# reset_final_rev01.net
KiCad netlist of a schematic drawn in EAGLE
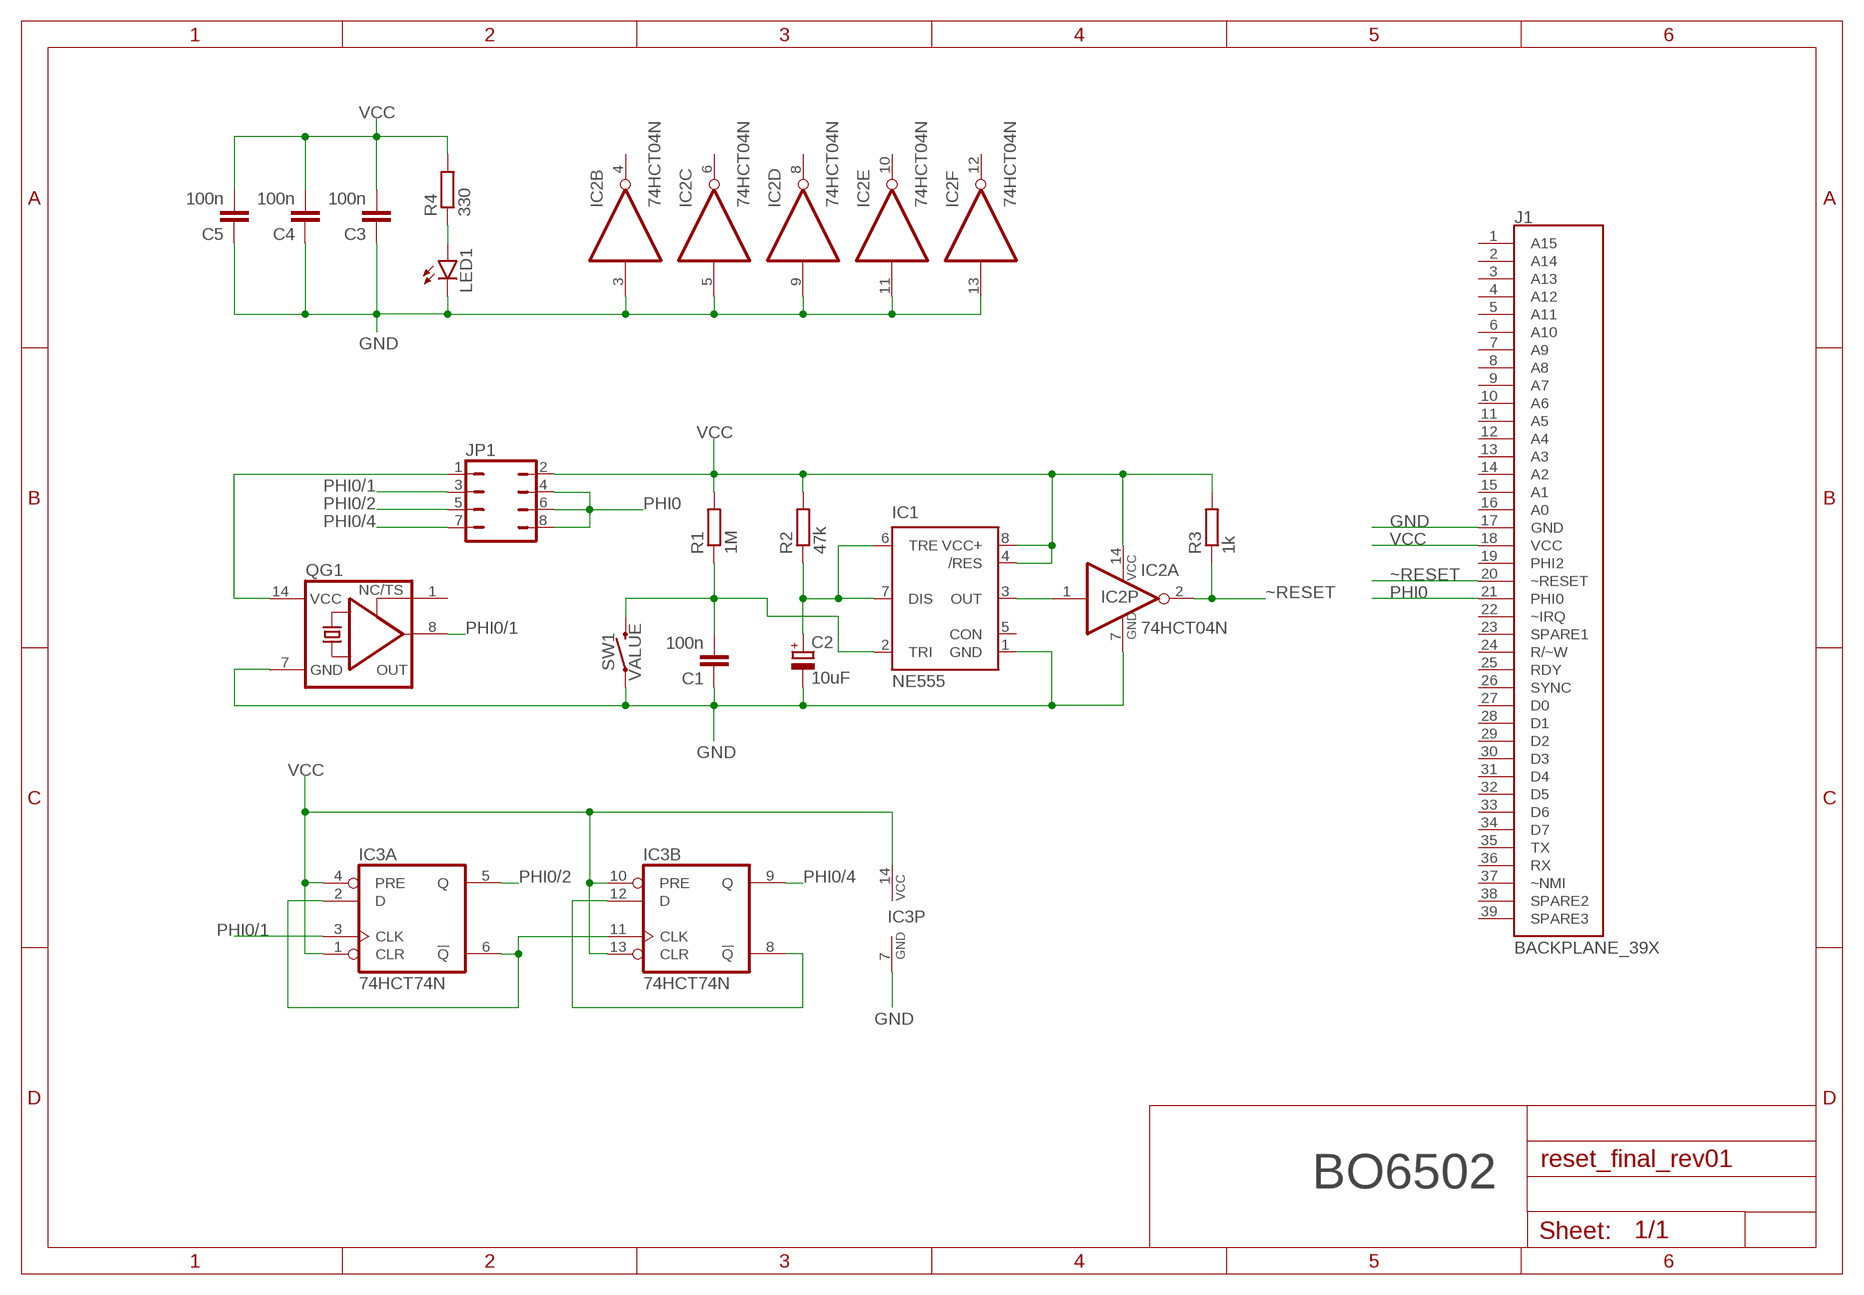
[diagram p0: schematic, sheet 1]

(export (version "E")
  (design (tool "Eeschema 10.0.6"))
  (components
    (comp (ref "C1")
      (value "100n")
      (footprint "eagle-import:C025-025X050")
      (libsource (lib "eagle-import") (part "C-EU025-025X050"))
    )
    (comp (ref "C2")
      (value "10uF")
      (footprint "eagle-import:B45181A")
      (libsource (lib "eagle-import") (part "CPOL-EUB45181A"))
    )
    (comp (ref "C3")
      (value "100n")
      (footprint "eagle-import:C025-025X050")
      (libsource (lib "eagle-import") (part "C-EU025-025X050"))
    )
    (comp (ref "C4")
      (value "100n")
      (footprint "eagle-import:C025-025X050")
      (libsource (lib "eagle-import") (part "C-EU025-025X050"))
    )
    (comp (ref "C5")
      (value "100n")
      (footprint "eagle-import:C025-025X050")
      (libsource (lib "eagle-import") (part "C-EU025-025X050"))
    )
    (comp (ref "IC1")
      (value "NE555")
      (footprint "eagle-import:DIL-08")
      (fields (field (name "MF") "Arrow Electronics") (field (name "MPN") "NE555N"))
      (libsource (lib "eagle-import") (part "NE555"))
    )
    (comp (ref "IC2")
      (value "74HCT04N")
      (footprint "eagle-import:DIL14")
      (libsource (lib "eagle-import") (part "7404NHCT"))
    )
    (comp (ref "IC3")
      (value "74HCT74N")
      (footprint "eagle-import:DIL14")
      (libsource (lib "eagle-import") (part "7474NHCT"))
    )
    (comp (ref "J1")
      (value "BACKPLANE_39X")
      (footprint "eagle-import:BP_39X")
      (fields
        (field (name "PIN_1") "A15")
        (field (name "PIN_2") "A14")
        (field (name "PIN_3") "A13")
        (field (name "PIN_4") "A12")
        (field (name "PIN_5") "A11")
        (field (name "PIN_6") "A10")
        (field (name "PIN_7") "A9")
        (field (name "PIN_8") "A8")
        (field (name "PIN_9") "A7")
      )
      (libsource (lib "eagle-import") (part "BACKPLANE_39X"))
    )
    (comp (ref "JP1")
      (value "JP4Q")
      (footprint "eagle-import:JP4Q")
      (libsource (lib "eagle-import") (part "JP4Q"))
    )
    (comp (ref "LED1")
      (value "LED5MM")
      (footprint "eagle-import:LED5MM")
      (libsource (lib "eagle-import") (part "LED5MM"))
    )
    (comp (ref "QG1")
      (value "XO-14")
      (footprint "eagle-import:DIL14S")
      (libsource (lib "eagle-import") (part "XO-14"))
    )
    (comp (ref "R1")
      (value "1M")
      (footprint "eagle-import:0207_10")
      (libsource (lib "eagle-import") (part "R-EU_0207/10"))
    )
    (comp (ref "R2")
      (value "47k")
      (footprint "eagle-import:0207_10")
      (libsource (lib "eagle-import") (part "R-EU_0207/10"))
    )
    (comp (ref "R3")
      (value "1k")
      (footprint "eagle-import:0207_10")
      (libsource (lib "eagle-import") (part "R-EU_0207/10"))
    )
    (comp (ref "R4")
      (value "330")
      (footprint "eagle-import:0207_10")
      (libsource (lib "eagle-import") (part "R-EU_0207/10"))
    )
    (comp (ref "SW1")
      (value "MOMENTARY-SWITCH-SPST-PTH-6.0MM-KIT")
      (footprint "eagle-import:TACTILE_SWITCH_PTH_6.0MM_KIT")
      (libsource (lib "eagle-import") (part "MOMENTARY-SWITCH-SPST-PTH-6.0MM-KIT"))
    )
  )
  (nets
    (net (code "1") (name "/GND") (class "Default")
      (node (ref "C1") (pin "1") (pinfunction "1_1") (pintype "passive"))
      (node (ref "C2") (pin "-") (pinfunction "-_-") (pintype "passive"))
      (node (ref "C3") (pin "1") (pinfunction "1_1") (pintype "passive"))
      (node (ref "C4") (pin "1") (pinfunction "1_1") (pintype "passive"))
      (node (ref "C5") (pin "1") (pinfunction "1_1") (pintype "passive"))
      (node (ref "IC1") (pin "1") (pinfunction "GND_1") (pintype "power_in"))
      (node (ref "IC2") (pin "11") (pinfunction "I_11") (pintype "input"))
      (node (ref "IC2") (pin "13") (pinfunction "I_13") (pintype "input"))
      (node (ref "IC2") (pin "3") (pinfunction "I_3") (pintype "input"))
      (node (ref "IC2") (pin "5") (pinfunction "I_5") (pintype "input"))
      (node (ref "IC2") (pin "7") (pinfunction "GND_7") (pintype "power_in"))
      (node (ref "IC2") (pin "9") (pinfunction "I_9") (pintype "input"))
      (node (ref "IC3") (pin "7") (pinfunction "GND_7") (pintype "power_in"))
      (node (ref "J1") (pin "17") (pinfunction "GND_17") (pintype "bidirectional"))
      (node (ref "LED1") (pin "K") (pinfunction "C_K") (pintype "passive"))
      (node (ref "QG1") (pin "7") (pinfunction "GND_7") (pintype "power_in"))
      (node (ref "SW1") (pin "1") (pinfunction "1_1") (pintype "passive"))
    )
    (net (code "2") (name "/PHI0") (class "Default")
      (node (ref "J1") (pin "21") (pinfunction "PHI0_21") (pintype "bidirectional"))
      (node (ref "JP1") (pin "4") (pinfunction "4_4") (pintype "passive"))
      (node (ref "JP1") (pin "6") (pinfunction "6_6") (pintype "passive"))
      (node (ref "JP1") (pin "8") (pinfunction "8_8") (pintype "passive"))
    )
    (net (code "3") (name "/PHI0{slash}1") (class "Default")
      (node (ref "IC3") (pin "3") (pinfunction "CLK_3") (pintype "input"))
      (node (ref "JP1") (pin "3") (pinfunction "3_3") (pintype "passive"))
      (node (ref "QG1") (pin "8") (pinfunction "OUT_8") (pintype "output"))
    )
    (net (code "4") (name "/PHI0{slash}2") (class "Default")
      (node (ref "IC3") (pin "5") (pinfunction "Q_5") (pintype "output"))
      (node (ref "JP1") (pin "5") (pinfunction "5_5") (pintype "passive"))
    )
    (net (code "5") (name "/PHI0{slash}4") (class "Default")
      (node (ref "IC3") (pin "9") (pinfunction "Q_9") (pintype "output"))
      (node (ref "JP1") (pin "7") (pinfunction "7_7") (pintype "passive"))
    )
    (net (code "6") (name "/VCC") (class "Default")
      (node (ref "C3") (pin "2") (pinfunction "2_2") (pintype "passive"))
      (node (ref "C4") (pin "2") (pinfunction "2_2") (pintype "passive"))
      (node (ref "C5") (pin "2") (pinfunction "2_2") (pintype "passive"))
      (node (ref "IC1") (pin "4") (pinfunction "/RES_4") (pintype "input"))
      (node (ref "IC1") (pin "8") (pinfunction "VCC+_8") (pintype "power_in"))
      (node (ref "IC2") (pin "14") (pinfunction "VCC_14") (pintype "power_in"))
      (node (ref "IC3") (pin "1") (pinfunction "CLR_1") (pintype "input"))
      (node (ref "IC3") (pin "10") (pinfunction "PRE_10") (pintype "input"))
      (node (ref "IC3") (pin "13") (pinfunction "CLR_13") (pintype "input"))
      (node (ref "IC3") (pin "14") (pinfunction "VCC_14") (pintype "power_in"))
      (node (ref "IC3") (pin "4") (pinfunction "PRE_4") (pintype "input"))
      (node (ref "J1") (pin "18") (pinfunction "VCC_18") (pintype "bidirectional"))
      (node (ref "JP1") (pin "2") (pinfunction "2_2") (pintype "passive"))
      (node (ref "R1") (pin "2") (pinfunction "2_2") (pintype "passive"))
      (node (ref "R2") (pin "2") (pinfunction "2_2") (pintype "passive"))
      (node (ref "R3") (pin "2") (pinfunction "2_2") (pintype "passive"))
      (node (ref "R4") (pin "2") (pinfunction "2_2") (pintype "passive"))
    )
    (net (code "7") (name "/~{RESET}") (class "Default")
      (node (ref "IC2") (pin "2") (pinfunction "O_2") (pintype "output"))
      (node (ref "J1") (pin "20") (pinfunction "~{RESET}_20") (pintype "bidirectional"))
      (node (ref "R3") (pin "1") (pinfunction "1_1") (pintype "passive"))
    )
    (net (code "8") (name "Net-(IC1-DIS)") (class "Default")
      (node (ref "C2") (pin "+") (pinfunction "+_+") (pintype "passive"))
      (node (ref "IC1") (pin "6") (pinfunction "TRE_6") (pintype "input"))
      (node (ref "IC1") (pin "7") (pinfunction "DIS_7") (pintype "input"))
      (node (ref "R2") (pin "1") (pinfunction "1_1") (pintype "passive"))
    )
    (net (code "9") (name "Net-(IC1-OUT)") (class "Default")
      (node (ref "IC1") (pin "3") (pinfunction "OUT_3") (pintype "output"))
      (node (ref "IC2") (pin "1") (pinfunction "I_1") (pintype "input"))
    )
    (net (code "10") (name "Net-(IC1-TRI)") (class "Default")
      (node (ref "C1") (pin "2") (pinfunction "2_2") (pintype "passive"))
      (node (ref "IC1") (pin "2") (pinfunction "TRI_2") (pintype "input"))
      (node (ref "R1") (pin "1") (pinfunction "1_1") (pintype "passive"))
      (node (ref "SW1") (pin "3") (pinfunction "2_3") (pintype "passive"))
    )
    (net (code "11") (name "Net-(IC3A-D)") (class "Default")
      (node (ref "IC3") (pin "11") (pinfunction "CLK_11") (pintype "input"))
      (node (ref "IC3") (pin "2") (pinfunction "D_2") (pintype "input"))
      (node (ref "IC3") (pin "6") (pinfunction "~{Q}_6") (pintype "output"))
    )
    (net (code "12") (name "Net-(IC3B-D)") (class "Default")
      (node (ref "IC3") (pin "12") (pinfunction "D_12") (pintype "input"))
      (node (ref "IC3") (pin "8") (pinfunction "~{Q}_8") (pintype "output"))
    )
    (net (code "13") (name "Net-(LED1-PadA)") (class "Default")
      (node (ref "LED1") (pin "A") (pinfunction "A_A") (pintype "passive"))
      (node (ref "R4") (pin "1") (pinfunction "1_1") (pintype "passive"))
    )
    (net (code "14") (name "Net-(QG1-VCC)") (class "Default")
      (node (ref "JP1") (pin "1") (pinfunction "1_1") (pintype "passive"))
      (node (ref "QG1") (pin "14") (pinfunction "VCC_14") (pintype "power_in"))
    )
    (net (code "15") (name "unconnected-(IC1-CON-Pad5)") (class "Default")
      (node (ref "IC1") (pin "5") (pinfunction "CON_5") (pintype "input"))
    )
    (net (code "16") (name "unconnected-(IC2B-O-Pad4)") (class "Default")
      (node (ref "IC2") (pin "4") (pinfunction "O_4") (pintype "output"))
    )
    (net (code "17") (name "unconnected-(IC2C-O-Pad6)") (class "Default")
      (node (ref "IC2") (pin "6") (pinfunction "O_6") (pintype "output"))
    )
    (net (code "18") (name "unconnected-(IC2D-O-Pad8)") (class "Default")
      (node (ref "IC2") (pin "8") (pinfunction "O_8") (pintype "output"))
    )
    (net (code "19") (name "unconnected-(IC2E-O-Pad10)") (class "Default")
      (node (ref "IC2") (pin "10") (pinfunction "O_10") (pintype "output"))
    )
    (net (code "20") (name "unconnected-(IC2F-O-Pad12)") (class "Default")
      (node (ref "IC2") (pin "12") (pinfunction "O_12") (pintype "output"))
    )
    (net (code "21") (name "unconnected-(J1-A0-Pad16)") (class "Default")
      (node (ref "J1") (pin "16") (pinfunction "A0_16") (pintype "bidirectional"))
    )
    (net (code "22") (name "unconnected-(J1-A1-Pad15)") (class "Default")
      (node (ref "J1") (pin "15") (pinfunction "A1_15") (pintype "bidirectional"))
    )
    (net (code "23") (name "unconnected-(J1-A2-Pad14)") (class "Default")
      (node (ref "J1") (pin "14") (pinfunction "A2_14") (pintype "bidirectional"))
    )
    (net (code "24") (name "unconnected-(J1-A3-Pad13)") (class "Default")
      (node (ref "J1") (pin "13") (pinfunction "A3_13") (pintype "bidirectional"))
    )
    (net (code "25") (name "unconnected-(J1-A4-Pad12)") (class "Default")
      (node (ref "J1") (pin "12") (pinfunction "A4_12") (pintype "bidirectional"))
    )
    (net (code "26") (name "unconnected-(J1-A5-Pad11)") (class "Default")
      (node (ref "J1") (pin "11") (pinfunction "A5_11") (pintype "bidirectional"))
    )
    (net (code "27") (name "unconnected-(J1-A6-Pad10)") (class "Default")
      (node (ref "J1") (pin "10") (pinfunction "A6_10") (pintype "bidirectional"))
    )
    (net (code "28") (name "unconnected-(J1-A7-Pad9)") (class "Default")
      (node (ref "J1") (pin "9") (pinfunction "A7_9") (pintype "bidirectional"))
    )
    (net (code "29") (name "unconnected-(J1-A8-Pad8)") (class "Default")
      (node (ref "J1") (pin "8") (pinfunction "A8_8") (pintype "bidirectional"))
    )
    (net (code "30") (name "unconnected-(J1-A9-Pad7)") (class "Default")
      (node (ref "J1") (pin "7") (pinfunction "A9_7") (pintype "bidirectional"))
    )
    (net (code "31") (name "unconnected-(J1-A10-Pad6)") (class "Default")
      (node (ref "J1") (pin "6") (pinfunction "A10_6") (pintype "bidirectional"))
    )
    (net (code "32") (name "unconnected-(J1-A11-Pad5)") (class "Default")
      (node (ref "J1") (pin "5") (pinfunction "A11_5") (pintype "bidirectional"))
    )
    (net (code "33") (name "unconnected-(J1-A12-Pad4)") (class "Default")
      (node (ref "J1") (pin "4") (pinfunction "A12_4") (pintype "bidirectional"))
    )
    (net (code "34") (name "unconnected-(J1-A13-Pad3)") (class "Default")
      (node (ref "J1") (pin "3") (pinfunction "A13_3") (pintype "bidirectional"))
    )
    (net (code "35") (name "unconnected-(J1-A14-Pad2)") (class "Default")
      (node (ref "J1") (pin "2") (pinfunction "A14_2") (pintype "bidirectional"))
    )
    (net (code "36") (name "unconnected-(J1-A15-Pad1)") (class "Default")
      (node (ref "J1") (pin "1") (pinfunction "A15_1") (pintype "bidirectional"))
    )
    (net (code "37") (name "unconnected-(J1-D0-Pad27)") (class "Default")
      (node (ref "J1") (pin "27") (pinfunction "D0_27") (pintype "bidirectional"))
    )
    (net (code "38") (name "unconnected-(J1-D1-Pad28)") (class "Default")
      (node (ref "J1") (pin "28") (pinfunction "D1_28") (pintype "bidirectional"))
    )
    (net (code "39") (name "unconnected-(J1-D2-Pad29)") (class "Default")
      (node (ref "J1") (pin "29") (pinfunction "D2_29") (pintype "bidirectional"))
    )
    (net (code "40") (name "unconnected-(J1-D3-Pad30)") (class "Default")
      (node (ref "J1") (pin "30") (pinfunction "D3_30") (pintype "bidirectional"))
    )
    (net (code "41") (name "unconnected-(J1-D4-Pad31)") (class "Default")
      (node (ref "J1") (pin "31") (pinfunction "D4_31") (pintype "bidirectional"))
    )
    (net (code "42") (name "unconnected-(J1-D5-Pad32)") (class "Default")
      (node (ref "J1") (pin "32") (pinfunction "D5_32") (pintype "bidirectional"))
    )
    (net (code "43") (name "unconnected-(J1-D6-Pad33)") (class "Default")
      (node (ref "J1") (pin "33") (pinfunction "D6_33") (pintype "bidirectional"))
    )
    (net (code "44") (name "unconnected-(J1-D7-Pad34)") (class "Default")
      (node (ref "J1") (pin "34") (pinfunction "D7_34") (pintype "bidirectional"))
    )
    (net (code "45") (name "unconnected-(J1-PHI2-Pad19)") (class "Default")
      (node (ref "J1") (pin "19") (pinfunction "PHI2_19") (pintype "bidirectional"))
    )
    (net (code "46") (name "unconnected-(J1-RDY-Pad25)") (class "Default")
      (node (ref "J1") (pin "25") (pinfunction "RDY_25") (pintype "bidirectional"))
    )
    (net (code "47") (name "unconnected-(J1-RX-Pad36)") (class "Default")
      (node (ref "J1") (pin "36") (pinfunction "RX_36") (pintype "bidirectional"))
    )
    (net (code "48") (name "unconnected-(J1-R{slash}~{W}-Pad24)") (class "Default")
      (node (ref "J1") (pin "24") (pinfunction "R/~{W}_24") (pintype "bidirectional"))
    )
    (net (code "49") (name "unconnected-(J1-SPARE1-Pad23)") (class "Default")
      (node (ref "J1") (pin "23") (pinfunction "SPARE1_23") (pintype "bidirectional"))
    )
    (net (code "50") (name "unconnected-(J1-SPARE2-Pad38)") (class "Default")
      (node (ref "J1") (pin "38") (pinfunction "SPARE2_38") (pintype "bidirectional"))
    )
    (net (code "51") (name "unconnected-(J1-SPARE3-Pad39)") (class "Default")
      (node (ref "J1") (pin "39") (pinfunction "SPARE3_39") (pintype "bidirectional"))
    )
    (net (code "52") (name "unconnected-(J1-SYNC-Pad26)") (class "Default")
      (node (ref "J1") (pin "26") (pinfunction "SYNC_26") (pintype "bidirectional"))
    )
    (net (code "53") (name "unconnected-(J1-TX-Pad35)") (class "Default")
      (node (ref "J1") (pin "35") (pinfunction "TX_35") (pintype "bidirectional"))
    )
    (net (code "54") (name "unconnected-(J1-~{IRQ}-Pad22)") (class "Default")
      (node (ref "J1") (pin "22") (pinfunction "~{IRQ}_22") (pintype "bidirectional"))
    )
    (net (code "55") (name "unconnected-(J1-~{NMI}-Pad37)") (class "Default")
      (node (ref "J1") (pin "37") (pinfunction "~{NMI}_37") (pintype "bidirectional"))
    )
    (net (code "56") (name "unconnected-(QG1-TS-Pad1)") (class "Default")
      (node (ref "QG1") (pin "1") (pinfunction "TS_1") (pintype "passive"))
    )
  )
)
